# SparkFun_ADMP401-Breakout.net
KiCad netlist of a schematic drawn in EAGLE
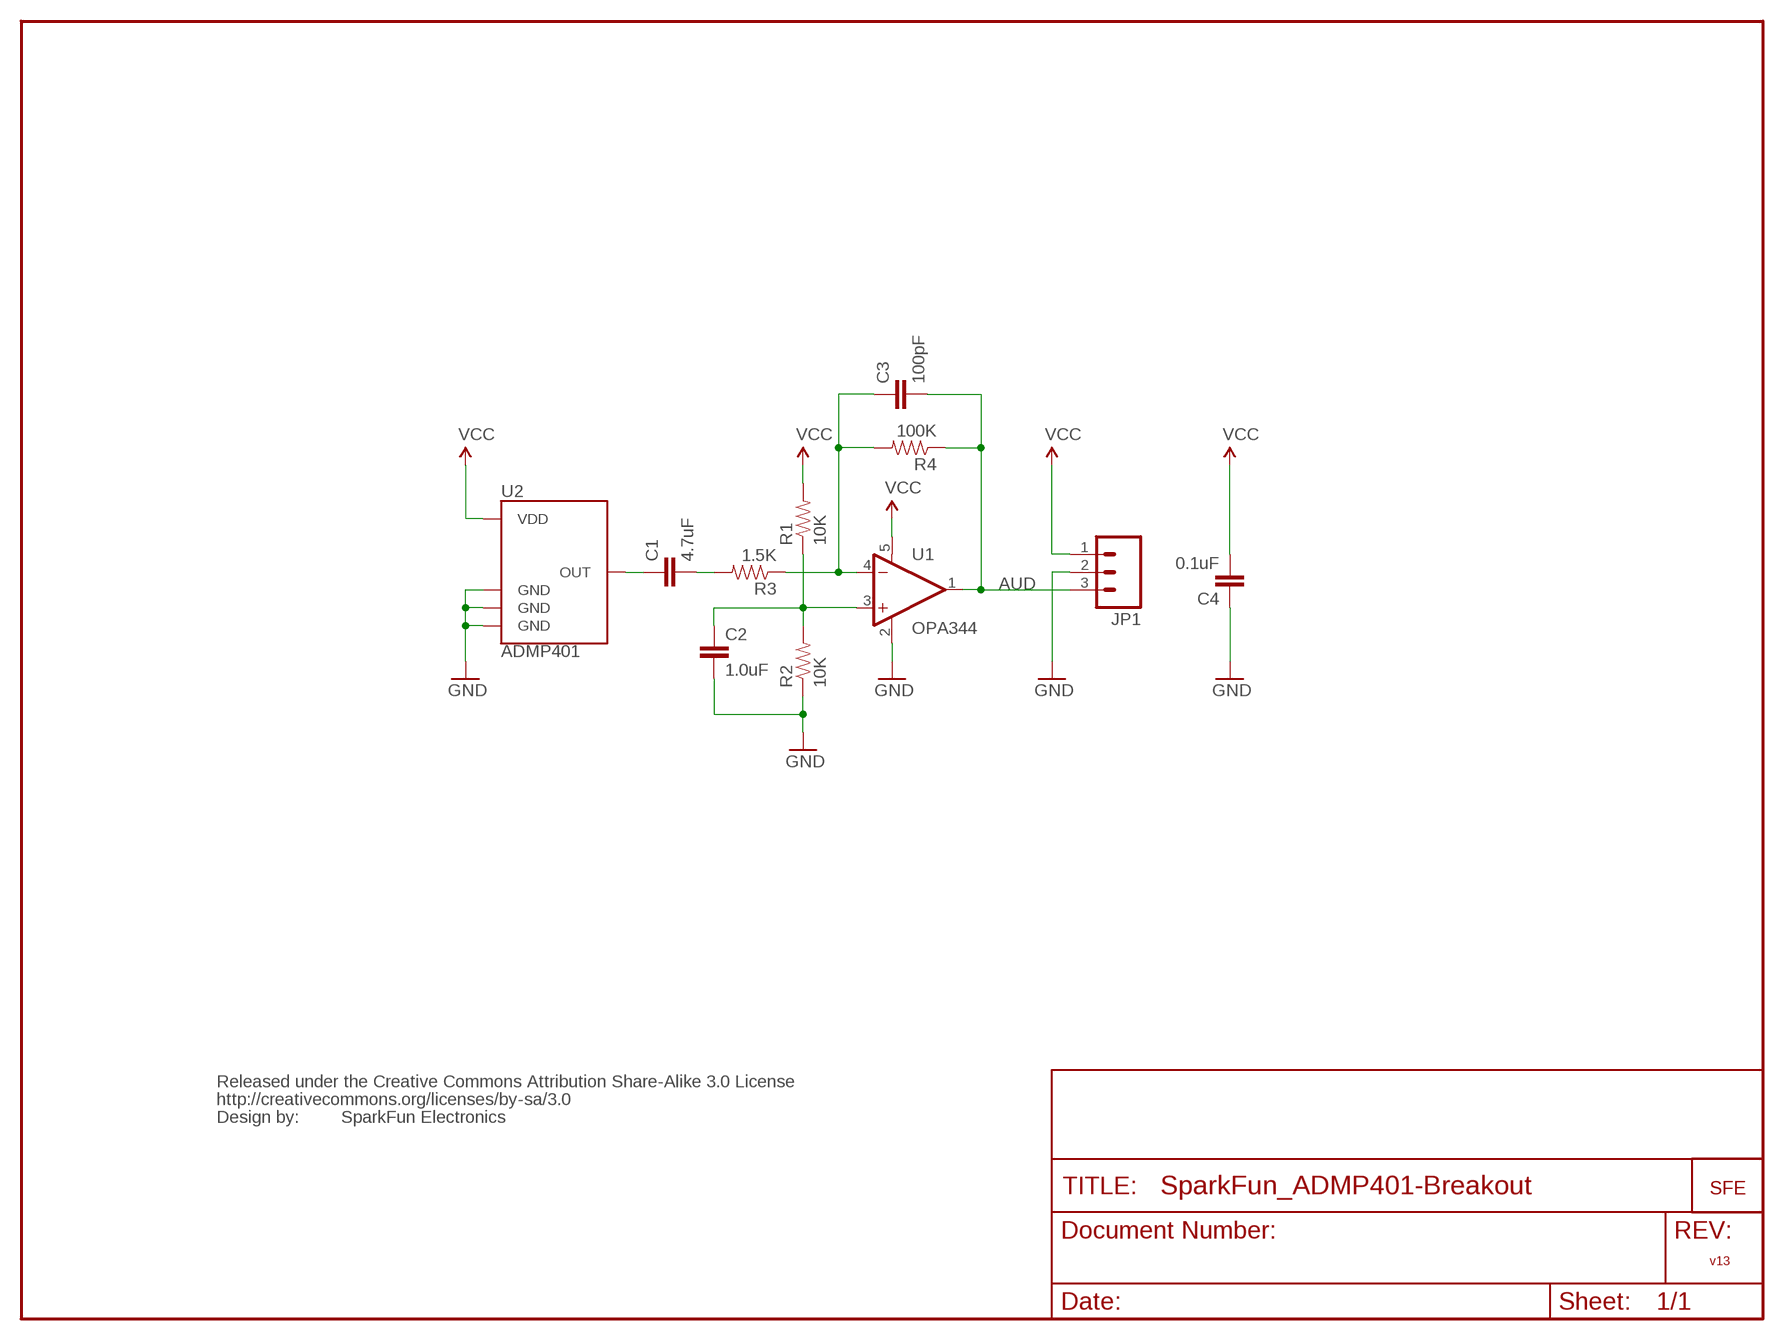
[diagram p0: schematic, sheet 1]

(export (version "E")
  (design (tool "Eeschema 10.0.6"))
  (components
    (comp (ref "C1")
      (value "4.7uF")
      (footprint "eagle-import:0402-CAP")
      (libsource (lib "eagle-import") (part "CAP0402-CAP"))
    )
    (comp (ref "C2")
      (value "1.0uF")
      (footprint "eagle-import:0402-CAP")
      (libsource (lib "eagle-import") (part "CAP0402-CAP"))
    )
    (comp (ref "C3")
      (value "100pF")
      (footprint "eagle-import:0402-CAP")
      (libsource (lib "eagle-import") (part "CAP0402-CAP"))
    )
    (comp (ref "C4")
      (value "0.1uF")
      (footprint "eagle-import:0402-CAP")
      (libsource (lib "eagle-import") (part "CAP0402-CAP"))
    )
    (comp (ref "JP1")
      (value "M03PTH")
      (footprint "eagle-import:1X03")
      (libsource (lib "eagle-import") (part "M03PTH"))
    )
    (comp (ref "R1")
      (value "10K")
      (footprint "eagle-import:0402-RES")
      (libsource (lib "eagle-import") (part "RESISTOR0402-RES"))
    )
    (comp (ref "R2")
      (value "10K")
      (footprint "eagle-import:0402-RES")
      (libsource (lib "eagle-import") (part "RESISTOR0402-RES"))
    )
    (comp (ref "R3")
      (value "1.5K")
      (footprint "eagle-import:0402-RES")
      (libsource (lib "eagle-import") (part "RESISTOR0402-RES"))
    )
    (comp (ref "R4")
      (value "100K")
      (footprint "eagle-import:0402-RES")
      (libsource (lib "eagle-import") (part "RESISTOR0402-RES"))
    )
    (comp (ref "U$1")
      (value "LOGO-SFESK")
      (footprint "eagle-import:SFE-LOGO-FLAME")
      (libsource (lib "eagle-import") (part "LOGO-SFESK"))
    )
    (comp (ref "U$2")
      (value "CREATIVE_COMMONS")
      (footprint "eagle-import:CREATIVE_COMMONS")
      (libsource (lib "eagle-import") (part "CREATIVE_COMMONS"))
    )
    (comp (ref "U1")
      (value "OPA344")
      (footprint "eagle-import:SOT23-5")
      (libsource (lib "eagle-import") (part "OPA344"))
    )
    (comp (ref "U2")
      (value "ADMP401")
      (footprint "eagle-import:ADMP401")
      (libsource (lib "eagle-import") (part "ADMP401"))
    )
  )
  (nets
    (net (code "1") (name "/AUD") (class "Default")
      (node (ref "C3") (pin "2") (pinfunction "2_2") (pintype "passive"))
      (node (ref "JP1") (pin "3") (pinfunction "3_3") (pintype "passive"))
      (node (ref "R4") (pin "1") (pinfunction "1_1") (pintype "passive"))
      (node (ref "U1") (pin "1") (pinfunction "OUT_1") (pintype "output"))
    )
    (net (code "2") (name "GND") (class "Default")
      (node (ref "C2") (pin "2") (pinfunction "2_2") (pintype "passive"))
      (node (ref "C4") (pin "1") (pinfunction "1_1") (pintype "passive"))
      (node (ref "JP1") (pin "2") (pinfunction "2_2") (pintype "passive"))
      (node (ref "R2") (pin "1") (pinfunction "1_1") (pintype "passive"))
      (node (ref "U1") (pin "2") (pinfunction "V-_2") (pintype "power_in"))
      (node (ref "U2") (pin "2") (pinfunction "GND_2") (pintype "bidirectional"))
      (node (ref "U2") (pin "4") (pinfunction "GND_4") (pintype "bidirectional"))
      (node (ref "U2") (pin "6") (pinfunction "GND_6") (pintype "bidirectional"))
    )
    (net (code "3") (name "Net-(C1-Pad2)") (class "Default")
      (node (ref "C1") (pin "2") (pinfunction "2_2") (pintype "passive"))
      (node (ref "R3") (pin "2") (pinfunction "2_2") (pintype "passive"))
    )
    (net (code "4") (name "Net-(U1-+IN)") (class "Default")
      (node (ref "C2") (pin "1") (pinfunction "1_1") (pintype "passive"))
      (node (ref "R1") (pin "1") (pinfunction "1_1") (pintype "passive"))
      (node (ref "R2") (pin "2") (pinfunction "2_2") (pintype "passive"))
      (node (ref "U1") (pin "3") (pinfunction "+IN_3") (pintype "input"))
    )
    (net (code "5") (name "Net-(U1--IN)") (class "Default")
      (node (ref "C3") (pin "1") (pinfunction "1_1") (pintype "passive"))
      (node (ref "R3") (pin "1") (pinfunction "1_1") (pintype "passive"))
      (node (ref "R4") (pin "2") (pinfunction "2_2") (pintype "passive"))
      (node (ref "U1") (pin "4") (pinfunction "-IN_4") (pintype "input"))
    )
    (net (code "6") (name "Net-(U2-OUT)") (class "Default")
      (node (ref "C1") (pin "1") (pinfunction "1_1") (pintype "passive"))
      (node (ref "U2") (pin "1") (pinfunction "OUT_1") (pintype "bidirectional"))
    )
    (net (code "7") (name "VCC") (class "Default")
      (node (ref "C4") (pin "2") (pinfunction "2_2") (pintype "passive"))
      (node (ref "JP1") (pin "1") (pinfunction "1_1") (pintype "passive"))
      (node (ref "R1") (pin "2") (pinfunction "2_2") (pintype "passive"))
      (node (ref "U1") (pin "5") (pinfunction "V+_5") (pintype "power_in"))
      (node (ref "U2") (pin "5") (pinfunction "VDD_5") (pintype "bidirectional"))
    )
  )
)
